# Registers_Module.net
KiCad netlist of a schematic drawn in Altium Designer
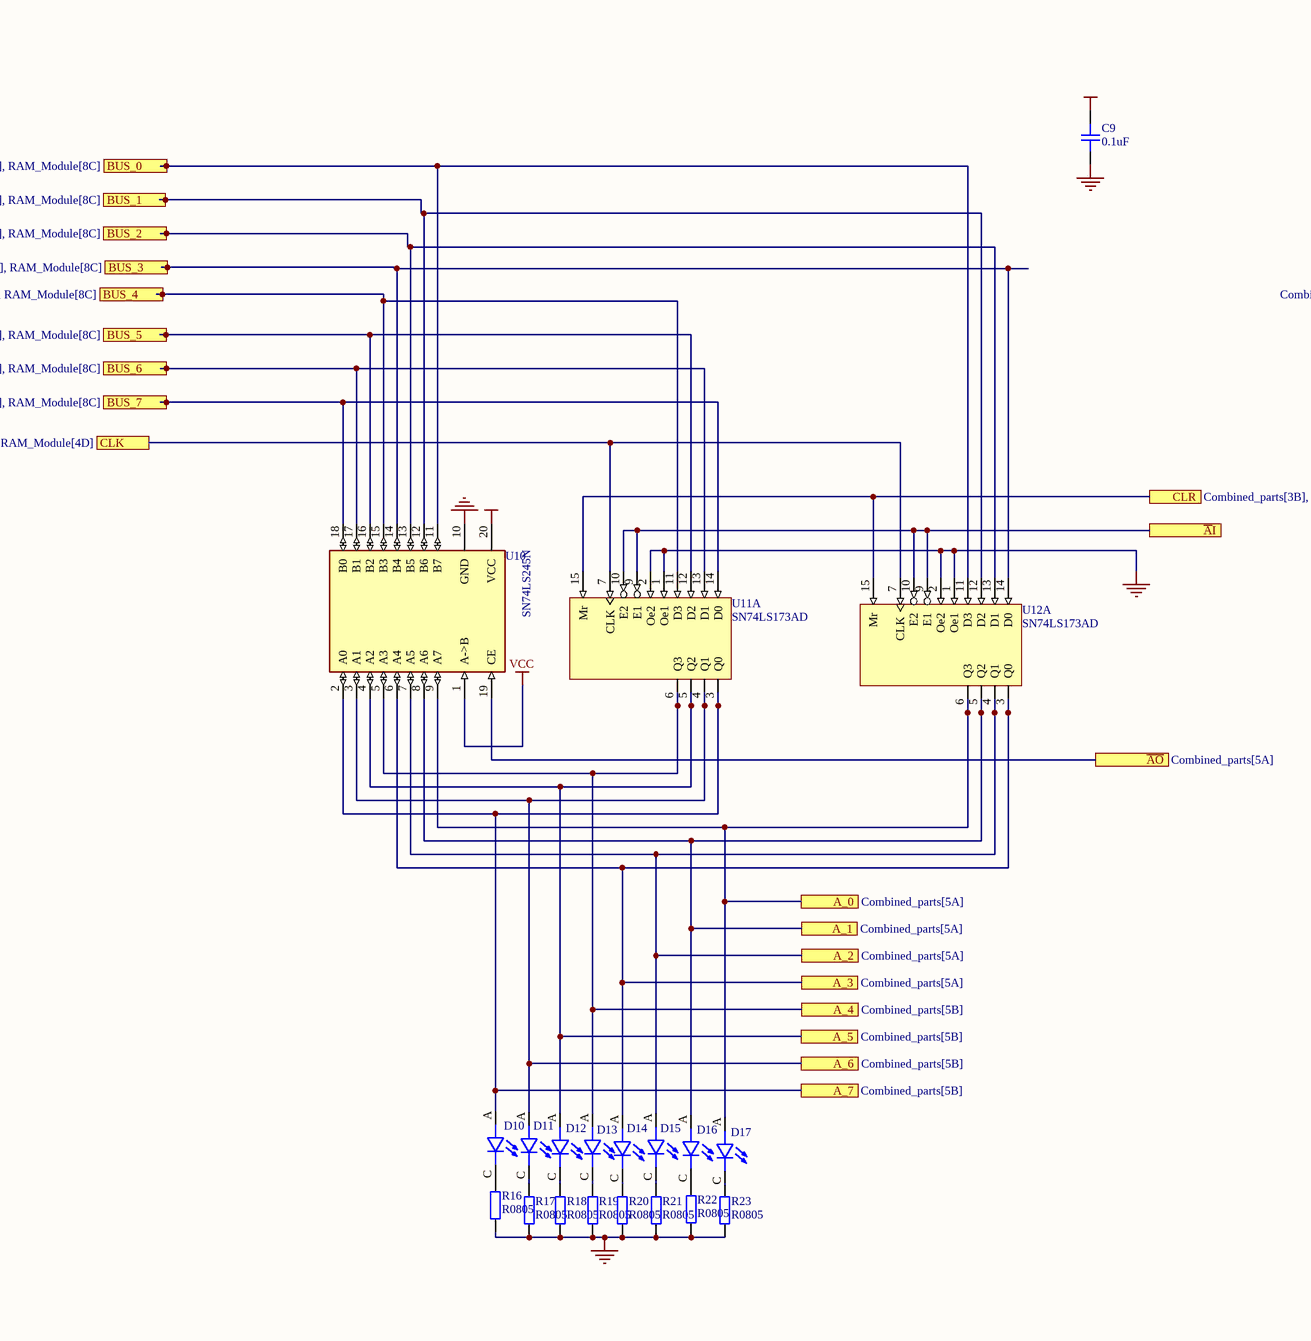
[diagram p0: Registers_Module.SchDoc, top left]
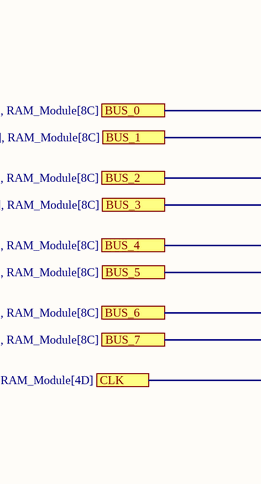
[diagram p1: Registers_Module.SchDoc, top middle]
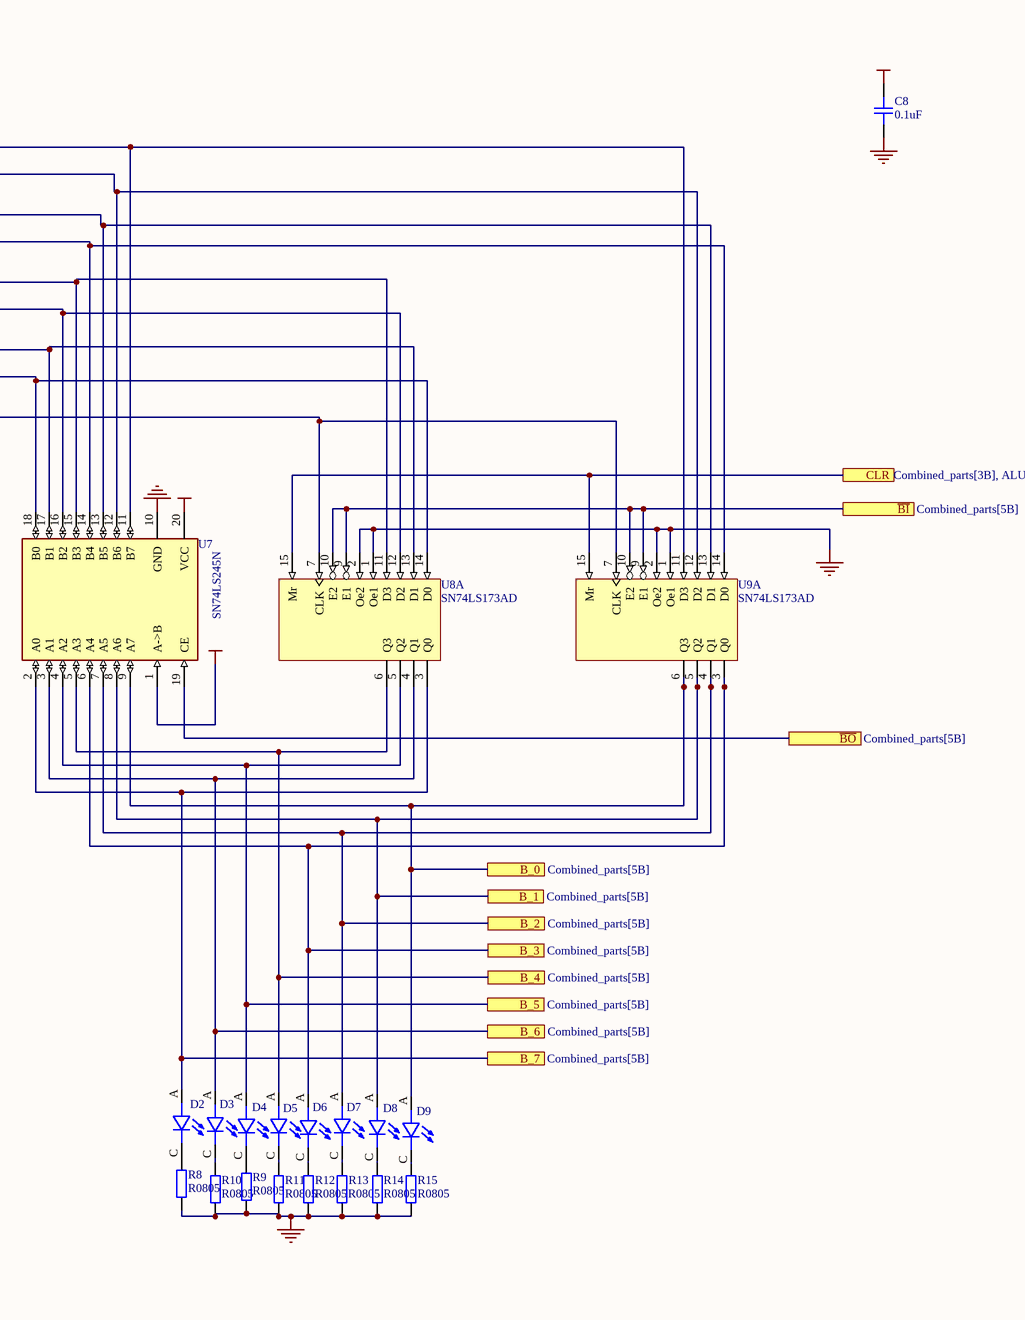
[diagram p2: Registers_Module.SchDoc, top right]
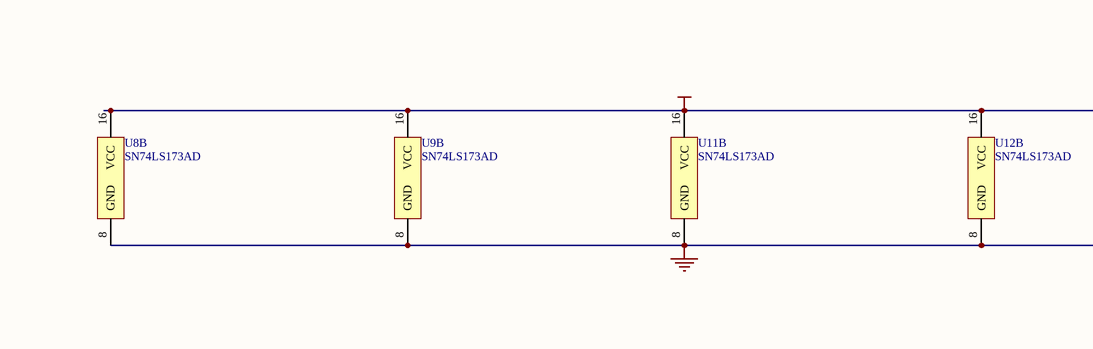
[diagram p3: Registers_Module.SchDoc, bottom left]
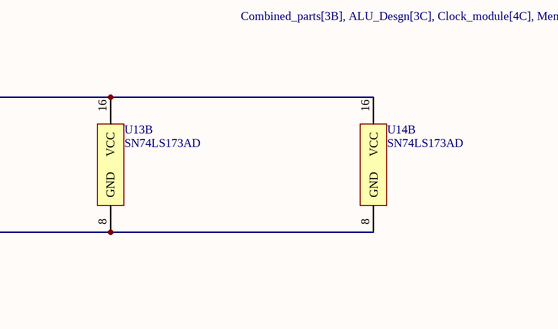
[diagram p4: Registers_Module.SchDoc, bottom middle]
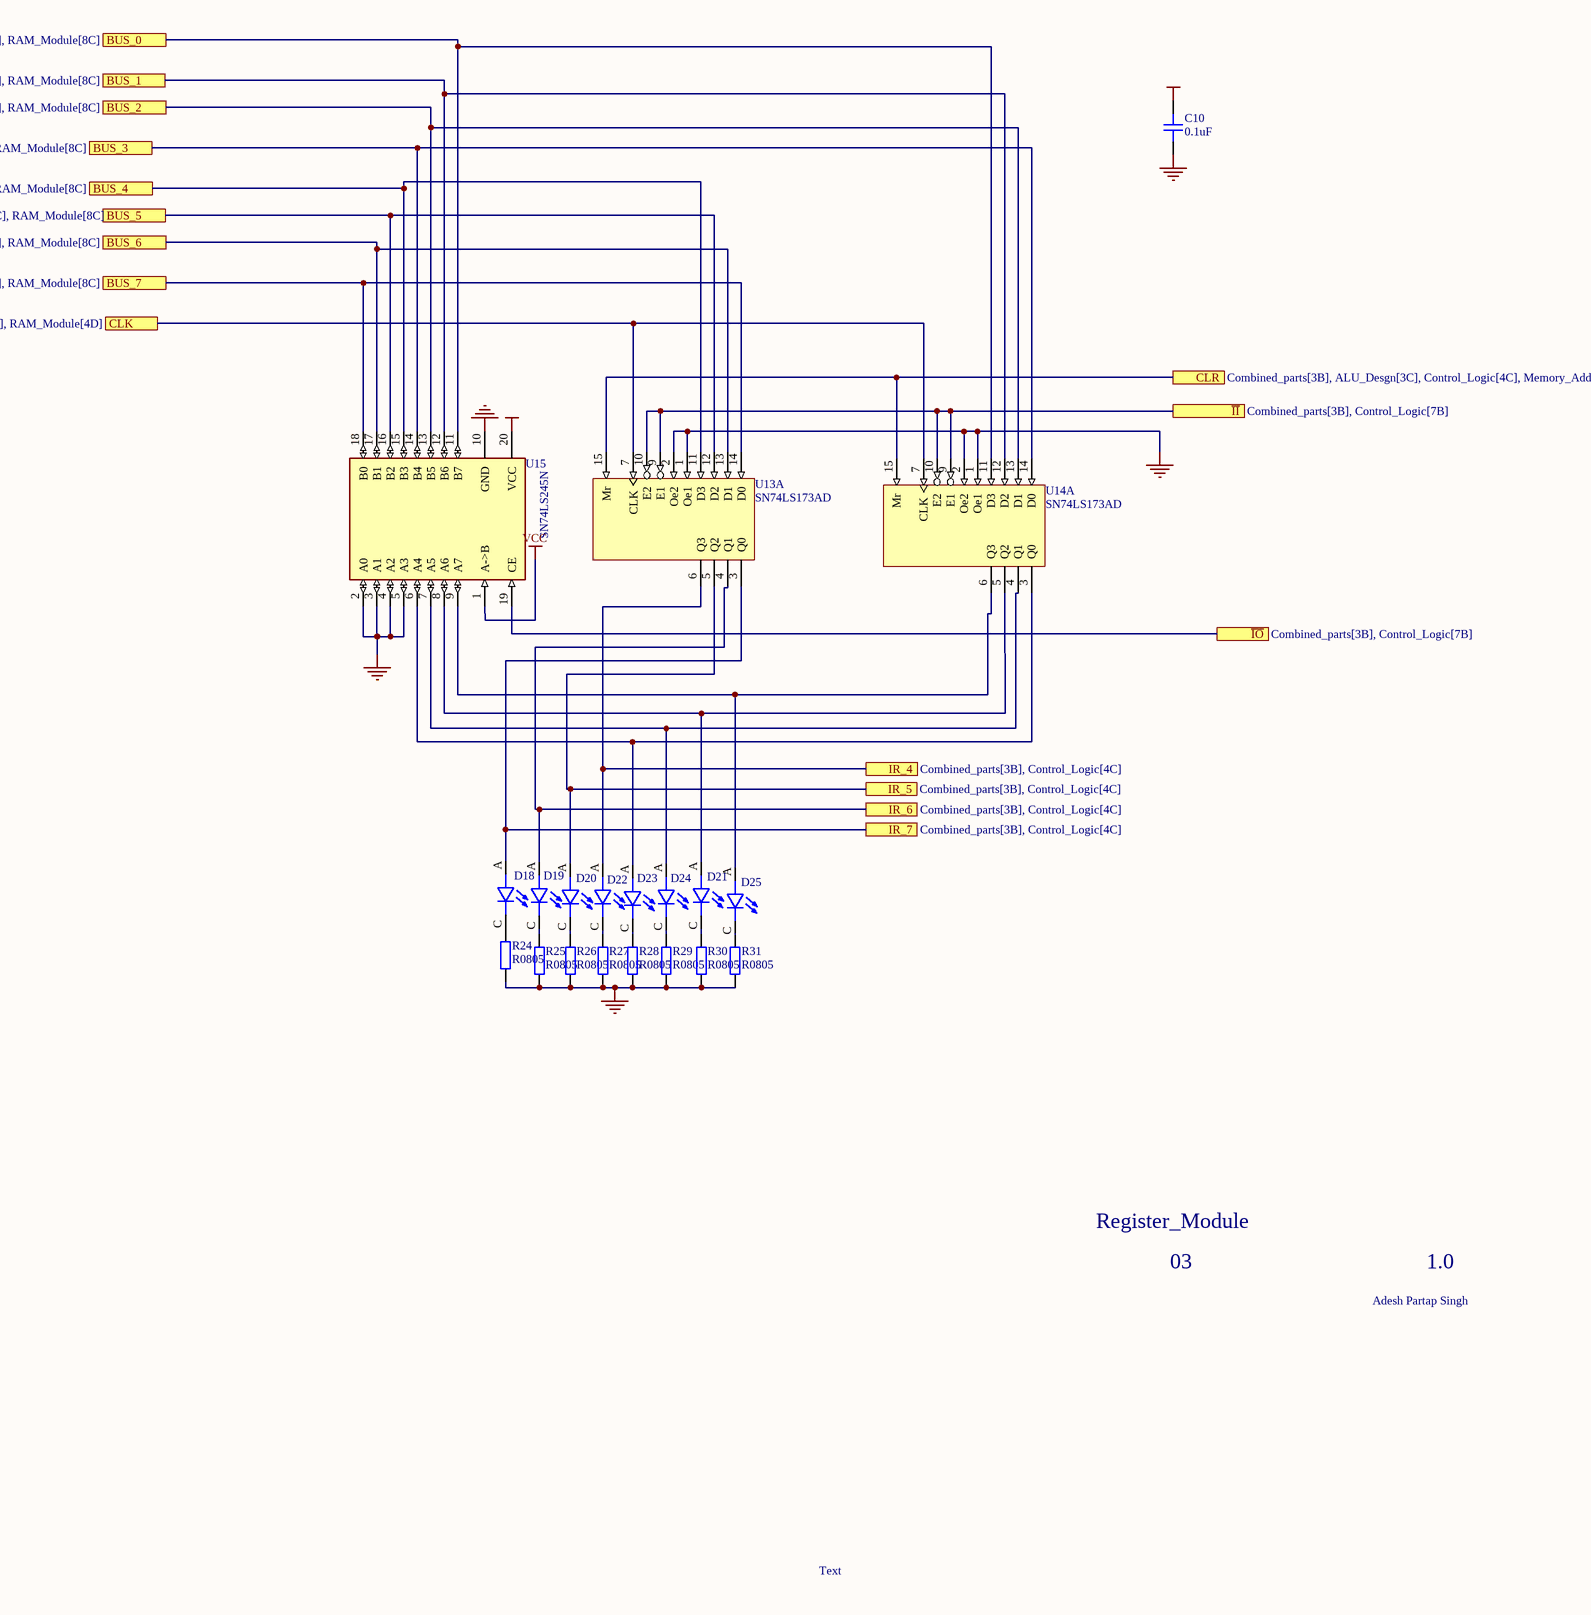
[diagram p5: Registers_Module.SchDoc, bottom right]

(export (version "E")
  (design (tool "Eeschema 10.0.6"))
  (components
    (comp (ref "C8")
      (value "0.1uF")
      (footprint "CAP_0805")
      (description "Capacitor SMD 0805")
      (libsource (lib "Schematic-Lib-PhilsLab") (part "CAP_0805"))
    )
    (comp (ref "C9")
      (value "0.1uF")
      (footprint "CAP_0805")
      (description "Capacitor SMD 0805")
      (libsource (lib "Schematic-Lib-PhilsLab") (part "CAP_0805"))
    )
    (comp (ref "C10")
      (value "0.1uF")
      (footprint "CAP_0805")
      (description "Capacitor SMD 0805")
      (libsource (lib "Schematic-Lib-PhilsLab") (part "CAP_0805"))
    )
    (comp (ref "D2")
      (value "L08R5000Q1")
      (footprint "LEDRD254W57D500H1070")
      (fields (field (name "MF") "LED Technology"))
      (libsource (lib "") (part "L08R5000Q1_1"))
    )
    (comp (ref "D3")
      (value "L08R5000Q1")
      (footprint "LEDRD254W57D500H1070")
      (fields (field (name "MF") "LED Technology"))
      (libsource (lib "") (part "L08R5000Q1_1"))
    )
    (comp (ref "D4")
      (value "L08R5000Q1")
      (footprint "LEDRD254W57D500H1070")
      (fields (field (name "MF") "LED Technology"))
      (libsource (lib "8BIT_COMP_LIB") (part "L08R5000Q1"))
    )
    (comp (ref "D5")
      (value "L08R5000Q1")
      (footprint "LEDRD254W57D500H1070")
      (fields (field (name "MF") "LED Technology"))
      (libsource (lib "") (part "L08R5000Q1_1"))
    )
    (comp (ref "D6")
      (value "L08R5000Q1")
      (footprint "LEDRD254W57D500H1070")
      (fields (field (name "MF") "LED Technology"))
      (libsource (lib "") (part "L08R5000Q1_1"))
    )
    (comp (ref "D7")
      (value "L08R5000Q1")
      (footprint "LEDRD254W57D500H1070")
      (fields (field (name "MF") "LED Technology"))
      (libsource (lib "") (part "L08R5000Q1_1"))
    )
    (comp (ref "D8")
      (value "L08R5000Q1")
      (footprint "LEDRD254W57D500H1070")
      (fields (field (name "MF") "LED Technology"))
      (libsource (lib "") (part "L08R5000Q1_1"))
    )
    (comp (ref "D9")
      (value "L08R5000Q1")
      (footprint "LEDRD254W57D500H1070")
      (fields (field (name "MF") "LED Technology"))
      (libsource (lib "") (part "L08R5000Q1_1"))
    )
    (comp (ref "D10")
      (value "L08R5000Q1")
      (footprint "LEDRD254W57D500H1070")
      (fields (field (name "MF") "LED Technology"))
      (libsource (lib "8BIT_COMP_LIB") (part "L08R5000Q1"))
    )
    (comp (ref "D11")
      (value "L08R5000Q1")
      (footprint "LEDRD254W57D500H1070")
      (fields (field (name "MF") "LED Technology"))
      (libsource (lib "8BIT_COMP_LIB") (part "L08R5000Q1"))
    )
    (comp (ref "D12")
      (value "L08R5000Q1")
      (footprint "LEDRD254W57D500H1070")
      (fields (field (name "MF") "LED Technology"))
      (libsource (lib "8BIT_COMP_LIB") (part "L08R5000Q1"))
    )
    (comp (ref "D13")
      (value "L08R5000Q1")
      (footprint "LEDRD254W57D500H1070")
      (fields (field (name "MF") "LED Technology"))
      (libsource (lib "8BIT_COMP_LIB") (part "L08R5000Q1"))
    )
    (comp (ref "D14")
      (value "L08R5000Q1")
      (footprint "LEDRD254W57D500H1070")
      (fields (field (name "MF") "LED Technology"))
      (libsource (lib "8BIT_COMP_LIB") (part "L08R5000Q1"))
    )
    (comp (ref "D15")
      (value "L08R5000Q1")
      (footprint "LEDRD254W57D500H1070")
      (fields (field (name "MF") "LED Technology"))
      (libsource (lib "8BIT_COMP_LIB") (part "L08R5000Q1"))
    )
    (comp (ref "D16")
      (value "L08R5000Q1")
      (footprint "LEDRD254W57D500H1070")
      (fields (field (name "MF") "LED Technology"))
      (libsource (lib "8BIT_COMP_LIB") (part "L08R5000Q1"))
    )
    (comp (ref "D17")
      (value "L08R5000Q1")
      (footprint "LEDRD254W57D500H1070")
      (fields (field (name "MF") "LED Technology"))
      (libsource (lib "8BIT_COMP_LIB") (part "L08R5000Q1"))
    )
    (comp (ref "D18")
      (value "L08R5000Q1")
      (footprint "LEDRD254W57D500H1070")
      (fields (field (name "MF") "LED Technology"))
      (libsource (lib "8BIT_COMP_LIB") (part "L08R5000Q1"))
    )
    (comp (ref "D19")
      (value "L08R5000Q1")
      (footprint "LEDRD254W57D500H1070")
      (fields (field (name "MF") "LED Technology"))
      (libsource (lib "8BIT_COMP_LIB") (part "L08R5000Q1"))
    )
    (comp (ref "D20")
      (value "L08R5000Q1")
      (footprint "LEDRD254W57D500H1070")
      (fields (field (name "MF") "LED Technology"))
      (libsource (lib "8BIT_COMP_LIB") (part "L08R5000Q1"))
    )
    (comp (ref "D21")
      (value "L08R5000Q1")
      (footprint "LEDRD254W57D500H1070")
      (fields (field (name "MF") "LED Technology"))
      (libsource (lib "8BIT_COMP_LIB") (part "L08R5000Q1"))
    )
    (comp (ref "D22")
      (value "L08R5000Q1")
      (footprint "LEDRD254W57D500H1070")
      (fields (field (name "MF") "LED Technology"))
      (libsource (lib "8BIT_COMP_LIB") (part "L08R5000Q1"))
    )
    (comp (ref "D23")
      (value "L08R5000Q1")
      (footprint "LEDRD254W57D500H1070")
      (fields (field (name "MF") "LED Technology"))
      (libsource (lib "8BIT_COMP_LIB") (part "L08R5000Q1"))
    )
    (comp (ref "D24")
      (value "L08R5000Q1")
      (footprint "LEDRD254W57D500H1070")
      (fields (field (name "MF") "LED Technology"))
      (libsource (lib "8BIT_COMP_LIB") (part "L08R5000Q1"))
    )
    (comp (ref "D25")
      (value "L08R5000Q1")
      (footprint "LEDRD254W57D500H1070")
      (fields (field (name "MF") "LED Technology"))
      (libsource (lib "8BIT_COMP_LIB") (part "L08R5000Q1"))
    )
    (comp (ref "R8")
      (value "R0805")
      (footprint "RES_0805")
      (description "Resistor SMD 0805")
      (libsource (lib "Schematic-Lib-PhilsLab") (part "RES_0805"))
    )
    (comp (ref "R9")
      (value "R0805")
      (footprint "RES_0805")
      (description "Resistor SMD 0805")
      (libsource (lib "Schematic-Lib-PhilsLab") (part "RES_0805"))
    )
    (comp (ref "R10")
      (value "R0805")
      (footprint "RES_0805")
      (description "Resistor SMD 0805")
      (libsource (lib "Schematic-Lib-PhilsLab") (part "RES_0805"))
    )
    (comp (ref "R11")
      (value "R0805")
      (footprint "RES_0805")
      (description "Resistor SMD 0805")
      (libsource (lib "Schematic-Lib-PhilsLab") (part "RES_0805"))
    )
    (comp (ref "R12")
      (value "R0805")
      (footprint "RES_0805")
      (description "Resistor SMD 0805")
      (libsource (lib "Schematic-Lib-PhilsLab") (part "RES_0805"))
    )
    (comp (ref "R13")
      (value "R0805")
      (footprint "RES_0805")
      (description "Resistor SMD 0805")
      (libsource (lib "Schematic-Lib-PhilsLab") (part "RES_0805"))
    )
    (comp (ref "R14")
      (value "R0805")
      (footprint "RES_0805")
      (description "Resistor SMD 0805")
      (libsource (lib "Schematic-Lib-PhilsLab") (part "RES_0805"))
    )
    (comp (ref "R15")
      (value "R0805")
      (footprint "RES_0805")
      (description "Resistor SMD 0805")
      (libsource (lib "Schematic-Lib-PhilsLab") (part "RES_0805"))
    )
    (comp (ref "R16")
      (value "R0805")
      (footprint "RES_0805")
      (description "Resistor SMD 0805")
      (libsource (lib "Schematic-Lib-PhilsLab") (part "RES_0805"))
    )
    (comp (ref "R17")
      (value "R0805")
      (footprint "RES_0805")
      (description "Resistor SMD 0805")
      (libsource (lib "Schematic-Lib-PhilsLab") (part "RES_0805"))
    )
    (comp (ref "R18")
      (value "R0805")
      (footprint "RES_0805")
      (description "Resistor SMD 0805")
      (libsource (lib "Schematic-Lib-PhilsLab") (part "RES_0805"))
    )
    (comp (ref "R19")
      (value "R0805")
      (footprint "RES_0805")
      (description "Resistor SMD 0805")
      (libsource (lib "Schematic-Lib-PhilsLab") (part "RES_0805"))
    )
    (comp (ref "R20")
      (value "R0805")
      (footprint "RES_0805")
      (description "Resistor SMD 0805")
      (libsource (lib "Schematic-Lib-PhilsLab") (part "RES_0805"))
    )
    (comp (ref "R21")
      (value "R0805")
      (footprint "RES_0805")
      (description "Resistor SMD 0805")
      (libsource (lib "Schematic-Lib-PhilsLab") (part "RES_0805"))
    )
    (comp (ref "R22")
      (value "R0805")
      (footprint "RES_0805")
      (description "Resistor SMD 0805")
      (libsource (lib "Schematic-Lib-PhilsLab") (part "RES_0805"))
    )
    (comp (ref "R23")
      (value "R0805")
      (footprint "RES_0805")
      (description "Resistor SMD 0805")
      (libsource (lib "Schematic-Lib-PhilsLab") (part "RES_0805"))
    )
    (comp (ref "R24")
      (value "R0805")
      (footprint "RES_0805")
      (description "Resistor SMD 0805")
      (libsource (lib "Schematic-Lib-PhilsLab") (part "RES_0805"))
    )
    (comp (ref "R25")
      (value "R0805")
      (footprint "RES_0805")
      (description "Resistor SMD 0805")
      (libsource (lib "Schematic-Lib-PhilsLab") (part "RES_0805"))
    )
    (comp (ref "R26")
      (value "R0805")
      (footprint "RES_0805")
      (description "Resistor SMD 0805")
      (libsource (lib "Schematic-Lib-PhilsLab") (part "RES_0805"))
    )
    (comp (ref "R27")
      (value "R0805")
      (footprint "RES_0805")
      (description "Resistor SMD 0805")
      (libsource (lib "Schematic-Lib-PhilsLab") (part "RES_0805"))
    )
    (comp (ref "R28")
      (value "R0805")
      (footprint "RES_0805")
      (description "Resistor SMD 0805")
      (libsource (lib "Schematic-Lib-PhilsLab") (part "RES_0805"))
    )
    (comp (ref "R29")
      (value "R0805")
      (footprint "RES_0805")
      (description "Resistor SMD 0805")
      (libsource (lib "Schematic-Lib-PhilsLab") (part "RES_0805"))
    )
    (comp (ref "R30")
      (value "R0805")
      (footprint "RES_0805")
      (description "Resistor SMD 0805")
      (libsource (lib "Schematic-Lib-PhilsLab") (part "RES_0805"))
    )
    (comp (ref "R31")
      (value "R0805")
      (footprint "RES_0805")
      (description "Resistor SMD 0805")
      (libsource (lib "Schematic-Lib-PhilsLab") (part "RES_0805"))
    )
    (comp (ref "U7")
      (value "SN74LS245N")
      (footprint "FP-N0020A-MFG")
      (description "IC TXRX NON-INVERT 5.25V 20DIP")
      (libsource (lib "8BIT_COMP_LIB") (part "CMP-1620-00419-3"))
    )
    (comp (ref "U8")
      (value "SN74LS173AD")
      (footprint "D0016A_N")
      (description "4-Bit D-type Registers with 3-State Outputs, D0016A, TUBE")
      (fields
        (field (name "GENERIC PART NUMBER") "SN74LS173A")
        (field (name "MANUFACTURER") "Texas Instruments")
      )
      (libsource (lib "") (part "CMP-1616-00008-3_1"))
    )
    (comp (ref "U9")
      (value "SN74LS173AD")
      (footprint "D0016A_N")
      (description "4-Bit D-type Registers with 3-State Outputs, D0016A, TUBE")
      (fields
        (field (name "GENERIC PART NUMBER") "SN74LS173A")
        (field (name "MANUFACTURER") "Texas Instruments")
      )
      (libsource (lib "") (part "CMP-1616-00008-3_1"))
    )
    (comp (ref "U10")
      (value "SN74LS245N")
      (footprint "FP-N0020A-MFG")
      (description "IC TXRX NON-INVERT 5.25V 20DIP")
      (libsource (lib "8BIT_COMP_LIB") (part "CMP-1620-00419-3"))
    )
    (comp (ref "U11")
      (value "SN74LS173AD")
      (footprint "D0016A_N")
      (description "4-Bit D-type Registers with 3-State Outputs, D0016A, TUBE")
      (fields
        (field (name "GENERIC PART NUMBER") "SN74LS173A")
        (field (name "MANUFACTURER") "Texas Instruments")
      )
      (libsource (lib "") (part "CMP-1616-00008-3_1"))
    )
    (comp (ref "U12")
      (value "SN74LS173AD")
      (footprint "D0016A_N")
      (description "4-Bit D-type Registers with 3-State Outputs, D0016A, TUBE")
      (fields
        (field (name "GENERIC PART NUMBER") "SN74LS173A")
        (field (name "MANUFACTURER") "Texas Instruments")
      )
      (libsource (lib "") (part "CMP-1616-00008-3_1"))
    )
    (comp (ref "U13")
      (value "SN74LS173AD")
      (footprint "D0016A_N")
      (description "4-Bit D-type Registers with 3-State Outputs, D0016A, TUBE")
      (fields
        (field (name "GENERIC PART NUMBER") "SN74LS173A")
        (field (name "MANUFACTURER") "Texas Instruments")
      )
      (libsource (lib "") (part "CMP-1616-00008-3_1"))
    )
    (comp (ref "U14")
      (value "SN74LS173AD")
      (footprint "D0016A_N")
      (description "4-Bit D-type Registers with 3-State Outputs, D0016A, TUBE")
      (fields
        (field (name "GENERIC PART NUMBER") "SN74LS173A")
        (field (name "MANUFACTURER") "Texas Instruments")
      )
      (libsource (lib "8BIT_COMP_LIB") (part "CMP-1616-00008-3"))
    )
    (comp (ref "U15")
      (value "SN74LS245N")
      (footprint "FP-N0020A-MFG")
      (description "IC TXRX NON-INVERT 5.25V 20DIP")
      (libsource (lib "8BIT_COMP_LIB") (part "CMP-1620-00419-3"))
    )
  )
  (nets
    (net (code "1") (name "/A_0") (class "Default")
      (node (ref "D17") (pin "A") (pinfunction "A_A") (pintype "passive"))
      (node (ref "U10") (pin "9") (pinfunction "A7_9") (pintype "bidirectional"))
      (node (ref "U12") (pin "6") (pinfunction "Q3_6") (pintype "tri_state"))
    )
    (net (code "2") (name "/A_1") (class "Default")
      (node (ref "D16") (pin "A") (pinfunction "A_A") (pintype "passive"))
      (node (ref "U10") (pin "8") (pinfunction "A6_8") (pintype "bidirectional"))
      (node (ref "U12") (pin "5") (pinfunction "Q2_5") (pintype "tri_state"))
    )
    (net (code "3") (name "/A_2") (class "Default")
      (node (ref "D15") (pin "A") (pinfunction "A_A") (pintype "passive"))
      (node (ref "U10") (pin "7") (pinfunction "A5_7") (pintype "bidirectional"))
      (node (ref "U12") (pin "4") (pinfunction "Q1_4") (pintype "tri_state"))
    )
    (net (code "4") (name "/A_3") (class "Default")
      (node (ref "D14") (pin "A") (pinfunction "A_A") (pintype "passive"))
      (node (ref "U10") (pin "6") (pinfunction "A4_6") (pintype "bidirectional"))
      (node (ref "U12") (pin "3") (pinfunction "Q0_3") (pintype "tri_state"))
    )
    (net (code "5") (name "/A_4") (class "Default")
      (node (ref "D13") (pin "A") (pinfunction "A_A") (pintype "passive"))
      (node (ref "U10") (pin "5") (pinfunction "A3_5") (pintype "bidirectional"))
      (node (ref "U11") (pin "6") (pinfunction "Q3_6") (pintype "tri_state"))
    )
    (net (code "6") (name "/A_5") (class "Default")
      (node (ref "D12") (pin "A") (pinfunction "A_A") (pintype "passive"))
      (node (ref "U10") (pin "4") (pinfunction "A2_4") (pintype "bidirectional"))
      (node (ref "U11") (pin "5") (pinfunction "Q2_5") (pintype "tri_state"))
    )
    (net (code "7") (name "/A_6") (class "Default")
      (node (ref "D11") (pin "A") (pinfunction "A_A") (pintype "passive"))
      (node (ref "U10") (pin "3") (pinfunction "A1_3") (pintype "bidirectional"))
      (node (ref "U11") (pin "4") (pinfunction "Q1_4") (pintype "tri_state"))
    )
    (net (code "8") (name "/A_7") (class "Default")
      (node (ref "D10") (pin "A") (pinfunction "A_A") (pintype "passive"))
      (node (ref "U10") (pin "2") (pinfunction "A0_2") (pintype "bidirectional"))
      (node (ref "U11") (pin "3") (pinfunction "Q0_3") (pintype "tri_state"))
    )
    (net (code "9") (name "/BUS_0") (class "Default")
      (node (ref "U10") (pin "11") (pinfunction "B7_11") (pintype "bidirectional"))
      (node (ref "U12") (pin "11") (pinfunction "D3_11") (pintype "input"))
      (node (ref "U14") (pin "11") (pinfunction "D3_11") (pintype "input"))
      (node (ref "U15") (pin "11") (pinfunction "B7_11") (pintype "bidirectional"))
      (node (ref "U7") (pin "11") (pinfunction "B7_11") (pintype "bidirectional"))
      (node (ref "U9") (pin "11") (pinfunction "D3_11") (pintype "input"))
    )
    (net (code "10") (name "/BUS_1") (class "Default")
      (node (ref "U10") (pin "12") (pinfunction "B6_12") (pintype "bidirectional"))
      (node (ref "U12") (pin "12") (pinfunction "D2_12") (pintype "input"))
      (node (ref "U14") (pin "12") (pinfunction "D2_12") (pintype "input"))
      (node (ref "U15") (pin "12") (pinfunction "B6_12") (pintype "bidirectional"))
      (node (ref "U7") (pin "12") (pinfunction "B6_12") (pintype "bidirectional"))
      (node (ref "U9") (pin "12") (pinfunction "D2_12") (pintype "input"))
    )
    (net (code "11") (name "/BUS_2") (class "Default")
      (node (ref "U10") (pin "13") (pinfunction "B5_13") (pintype "bidirectional"))
      (node (ref "U12") (pin "13") (pinfunction "D1_13") (pintype "input"))
      (node (ref "U14") (pin "13") (pinfunction "D1_13") (pintype "input"))
      (node (ref "U15") (pin "13") (pinfunction "B5_13") (pintype "bidirectional"))
      (node (ref "U7") (pin "13") (pinfunction "B5_13") (pintype "bidirectional"))
      (node (ref "U9") (pin "13") (pinfunction "D1_13") (pintype "input"))
    )
    (net (code "12") (name "/BUS_3") (class "Default")
      (node (ref "U10") (pin "14") (pinfunction "B4_14") (pintype "bidirectional"))
      (node (ref "U12") (pin "14") (pinfunction "D0_14") (pintype "input"))
      (node (ref "U14") (pin "14") (pinfunction "D0_14") (pintype "input"))
      (node (ref "U15") (pin "14") (pinfunction "B4_14") (pintype "bidirectional"))
      (node (ref "U7") (pin "14") (pinfunction "B4_14") (pintype "bidirectional"))
      (node (ref "U9") (pin "14") (pinfunction "D0_14") (pintype "input"))
    )
    (net (code "13") (name "/BUS_4") (class "Default")
      (node (ref "U10") (pin "15") (pinfunction "B3_15") (pintype "bidirectional"))
      (node (ref "U11") (pin "11") (pinfunction "D3_11") (pintype "input"))
      (node (ref "U13") (pin "11") (pinfunction "D3_11") (pintype "input"))
      (node (ref "U15") (pin "15") (pinfunction "B3_15") (pintype "bidirectional"))
      (node (ref "U7") (pin "15") (pinfunction "B3_15") (pintype "bidirectional"))
      (node (ref "U8") (pin "11") (pinfunction "D3_11") (pintype "input"))
    )
    (net (code "14") (name "/BUS_5") (class "Default")
      (node (ref "U10") (pin "16") (pinfunction "B2_16") (pintype "bidirectional"))
      (node (ref "U11") (pin "12") (pinfunction "D2_12") (pintype "input"))
      (node (ref "U13") (pin "12") (pinfunction "D2_12") (pintype "input"))
      (node (ref "U15") (pin "16") (pinfunction "B2_16") (pintype "bidirectional"))
      (node (ref "U7") (pin "16") (pinfunction "B2_16") (pintype "bidirectional"))
      (node (ref "U8") (pin "12") (pinfunction "D2_12") (pintype "input"))
    )
    (net (code "15") (name "/BUS_6") (class "Default")
      (node (ref "U10") (pin "17") (pinfunction "B1_17") (pintype "bidirectional"))
      (node (ref "U11") (pin "13") (pinfunction "D1_13") (pintype "input"))
      (node (ref "U13") (pin "13") (pinfunction "D1_13") (pintype "input"))
      (node (ref "U15") (pin "17") (pinfunction "B1_17") (pintype "bidirectional"))
      (node (ref "U7") (pin "17") (pinfunction "B1_17") (pintype "bidirectional"))
      (node (ref "U8") (pin "13") (pinfunction "D1_13") (pintype "input"))
    )
    (net (code "16") (name "/BUS_7") (class "Default")
      (node (ref "U10") (pin "18") (pinfunction "B0_18") (pintype "bidirectional"))
      (node (ref "U11") (pin "14") (pinfunction "D0_14") (pintype "input"))
      (node (ref "U13") (pin "14") (pinfunction "D0_14") (pintype "input"))
      (node (ref "U15") (pin "18") (pinfunction "B0_18") (pintype "bidirectional"))
      (node (ref "U7") (pin "18") (pinfunction "B0_18") (pintype "bidirectional"))
      (node (ref "U8") (pin "14") (pinfunction "D0_14") (pintype "input"))
    )
    (net (code "17") (name "/B_0") (class "Default")
      (node (ref "D9") (pin "A") (pinfunction "A_A") (pintype "passive"))
      (node (ref "U7") (pin "9") (pinfunction "A7_9") (pintype "bidirectional"))
      (node (ref "U9") (pin "6") (pinfunction "Q3_6") (pintype "tri_state"))
    )
    (net (code "18") (name "/B_1") (class "Default")
      (node (ref "D8") (pin "A") (pinfunction "A_A") (pintype "passive"))
      (node (ref "U7") (pin "8") (pinfunction "A6_8") (pintype "bidirectional"))
      (node (ref "U9") (pin "5") (pinfunction "Q2_5") (pintype "tri_state"))
    )
    (net (code "19") (name "/B_2") (class "Default")
      (node (ref "D7") (pin "A") (pinfunction "A_A") (pintype "passive"))
      (node (ref "U7") (pin "7") (pinfunction "A5_7") (pintype "bidirectional"))
      (node (ref "U9") (pin "4") (pinfunction "Q1_4") (pintype "tri_state"))
    )
    (net (code "20") (name "/B_3") (class "Default")
      (node (ref "D6") (pin "A") (pinfunction "A_A") (pintype "passive"))
      (node (ref "U7") (pin "6") (pinfunction "A4_6") (pintype "bidirectional"))
      (node (ref "U9") (pin "3") (pinfunction "Q0_3") (pintype "tri_state"))
    )
    (net (code "21") (name "/B_4") (class "Default")
      (node (ref "D5") (pin "A") (pinfunction "A_A") (pintype "passive"))
      (node (ref "U7") (pin "5") (pinfunction "A3_5") (pintype "bidirectional"))
      (node (ref "U8") (pin "6") (pinfunction "Q3_6") (pintype "tri_state"))
    )
    (net (code "22") (name "/B_5") (class "Default")
      (node (ref "D4") (pin "A") (pinfunction "A_A") (pintype "passive"))
      (node (ref "U7") (pin "4") (pinfunction "A2_4") (pintype "bidirectional"))
      (node (ref "U8") (pin "5") (pinfunction "Q2_5") (pintype "tri_state"))
    )
    (net (code "23") (name "/B_6") (class "Default")
      (node (ref "D3") (pin "A") (pinfunction "A_A") (pintype "passive"))
      (node (ref "U7") (pin "3") (pinfunction "A1_3") (pintype "bidirectional"))
      (node (ref "U8") (pin "4") (pinfunction "Q1_4") (pintype "tri_state"))
    )
    (net (code "24") (name "/B_7") (class "Default")
      (node (ref "D2") (pin "A") (pinfunction "A_A") (pintype "passive"))
      (node (ref "U7") (pin "2") (pinfunction "A0_2") (pintype "bidirectional"))
      (node (ref "U8") (pin "3") (pinfunction "Q0_3") (pintype "tri_state"))
    )
    (net (code "25") (name "/CLK") (class "Default")
      (node (ref "U11") (pin "7") (pinfunction "CLK_7") (pintype "input"))
      (node (ref "U12") (pin "7") (pinfunction "CLK_7") (pintype "input"))
      (node (ref "U13") (pin "7") (pinfunction "CLK_7") (pintype "input"))
      (node (ref "U14") (pin "7") (pinfunction "CLK_7") (pintype "input"))
      (node (ref "U8") (pin "7") (pinfunction "CLK_7") (pintype "input"))
      (node (ref "U9") (pin "7") (pinfunction "CLK_7") (pintype "input"))
    )
    (net (code "26") (name "/CLR") (class "Default")
      (node (ref "U11") (pin "15") (pinfunction "Mr_15") (pintype "input"))
      (node (ref "U12") (pin "15") (pinfunction "Mr_15") (pintype "input"))
      (node (ref "U13") (pin "15") (pinfunction "Mr_15") (pintype "input"))
      (node (ref "U14") (pin "15") (pinfunction "Mr_15") (pintype "input"))
      (node (ref "U8") (pin "15") (pinfunction "Mr_15") (pintype "input"))
      (node (ref "U9") (pin "15") (pinfunction "Mr_15") (pintype "input"))
    )
    (net (code "27") (name "/IR_4") (class "Default")
      (node (ref "D22") (pin "A") (pinfunction "A_A") (pintype "passive"))
      (node (ref "U13") (pin "6") (pinfunction "Q3_6") (pintype "tri_state"))
    )
    (net (code "28") (name "/IR_5") (class "Default")
      (node (ref "D20") (pin "A") (pinfunction "A_A") (pintype "passive"))
      (node (ref "U13") (pin "5") (pinfunction "Q2_5") (pintype "tri_state"))
    )
    (net (code "29") (name "/IR_6") (class "Default")
      (node (ref "D19") (pin "A") (pinfunction "A_A") (pintype "passive"))
      (node (ref "U13") (pin "4") (pinfunction "Q1_4") (pintype "tri_state"))
    )
    (net (code "30") (name "/IR_7") (class "Default")
      (node (ref "D18") (pin "A") (pinfunction "A_A") (pintype "passive"))
      (node (ref "U13") (pin "3") (pinfunction "Q0_3") (pintype "tri_state"))
    )
    (net (code "31") (name "/~{AO}") (class "Default")
      (node (ref "U10") (pin "19") (pinfunction "CE_19") (pintype "input"))
    )
    (net (code "32") (name "/~{A}I") (class "Default")
      (node (ref "U11") (pin "10") (pinfunction "E2_10") (pintype "input"))
      (node (ref "U11") (pin "9") (pinfunction "E1_9") (pintype "input"))
      (node (ref "U12") (pin "10") (pinfunction "E2_10") (pintype "input"))
      (node (ref "U12") (pin "9") (pinfunction "E1_9") (pintype "input"))
    )
    (net (code "33") (name "/~{BI}") (class "Default")
      (node (ref "U8") (pin "10") (pinfunction "E2_10") (pintype "input"))
      (node (ref "U8") (pin "9") (pinfunction "E1_9") (pintype "input"))
      (node (ref "U9") (pin "10") (pinfunction "E2_10") (pintype "input"))
      (node (ref "U9") (pin "9") (pinfunction "E1_9") (pintype "input"))
    )
    (net (code "34") (name "/~{BO}") (class "Default")
      (node (ref "U7") (pin "19") (pinfunction "CE_19") (pintype "input"))
    )
    (net (code "35") (name "/~{II}") (class "Default")
      (node (ref "U13") (pin "10") (pinfunction "E2_10") (pintype "input"))
      (node (ref "U13") (pin "9") (pinfunction "E1_9") (pintype "input"))
      (node (ref "U14") (pin "10") (pinfunction "E2_10") (pintype "input"))
      (node (ref "U14") (pin "9") (pinfunction "E1_9") (pintype "input"))
    )
    (net (code "36") (name "/~{IO}") (class "Default")
      (node (ref "U15") (pin "19") (pinfunction "CE_19") (pintype "input"))
    )
    (net (code "37") (name "GND") (class "Default")
      (node (ref "C10") (pin "1") (pinfunction "1_1") (pintype "passive"))
      (node (ref "C8") (pin "1") (pinfunction "1_1") (pintype "passive"))
      (node (ref "C9") (pin "1") (pinfunction "1_1") (pintype "passive"))
      (node (ref "R10") (pin "1") (pinfunction "1_1") (pintype "passive"))
      (node (ref "R11") (pin "1") (pinfunction "1_1") (pintype "passive"))
      (node (ref "R12") (pin "1") (pinfunction "1_1") (pintype "passive"))
      (node (ref "R13") (pin "1") (pinfunction "1_1") (pintype "passive"))
      (node (ref "R14") (pin "1") (pinfunction "1_1") (pintype "passive"))
      (node (ref "R15") (pin "1") (pinfunction "1_1") (pintype "passive"))
      (node (ref "R16") (pin "1") (pinfunction "1_1") (pintype "passive"))
      (node (ref "R17") (pin "1") (pinfunction "1_1") (pintype "passive"))
      (node (ref "R18") (pin "1") (pinfunction "1_1") (pintype "passive"))
      (node (ref "R19") (pin "1") (pinfunction "1_1") (pintype "passive"))
      (node (ref "R20") (pin "1") (pinfunction "1_1") (pintype "passive"))
      (node (ref "R21") (pin "1") (pinfunction "1_1") (pintype "passive"))
      (node (ref "R22") (pin "1") (pinfunction "1_1") (pintype "passive"))
      (node (ref "R23") (pin "1") (pinfunction "1_1") (pintype "passive"))
      (node (ref "R24") (pin "1") (pinfunction "1_1") (pintype "passive"))
      (node (ref "R25") (pin "1") (pinfunction "1_1") (pintype "passive"))
      (node (ref "R26") (pin "1") (pinfunction "1_1") (pintype "passive"))
      (node (ref "R27") (pin "1") (pinfunction "1_1") (pintype "passive"))
      (node (ref "R28") (pin "1") (pinfunction "1_1") (pintype "passive"))
      (node (ref "R29") (pin "1") (pinfunction "1_1") (pintype "passive"))
      (node (ref "R30") (pin "1") (pinfunction "1_1") (pintype "passive"))
      (node (ref "R31") (pin "1") (pinfunction "1_1") (pintype "passive"))
      (node (ref "R8") (pin "1") (pinfunction "1_1") (pintype "passive"))
      (node (ref "R9") (pin "1") (pinfunction "1_1") (pintype "passive"))
      (node (ref "U10") (pin "10") (pinfunction "GND_10") (pintype "power_in"))
      (node (ref "U11") (pin "1") (pinfunction "Oe1_1") (pintype "input"))
      (node (ref "U11") (pin "2") (pinfunction "Oe2_2") (pintype "input"))
      (node (ref "U11") (pin "8") (pinfunction "GND_8") (pintype "power_in"))
      (node (ref "U12") (pin "1") (pinfunction "Oe1_1") (pintype "input"))
      (node (ref "U12") (pin "2") (pinfunction "Oe2_2") (pintype "input"))
      (node (ref "U12") (pin "8") (pinfunction "GND_8") (pintype "power_in"))
      (node (ref "U13") (pin "1") (pinfunction "Oe1_1") (pintype "input"))
      (node (ref "U13") (pin "2") (pinfunction "Oe2_2") (pintype "input"))
      (node (ref "U13") (pin "8") (pinfunction "GND_8") (pintype "power_in"))
      (node (ref "U14") (pin "1") (pinfunction "Oe1_1") (pintype "input"))
      (node (ref "U14") (pin "2") (pinfunction "Oe2_2") (pintype "input"))
      (node (ref "U14") (pin "8") (pinfunction "GND_8") (pintype "power_in"))
      (node (ref "U15") (pin "10") (pinfunction "GND_10") (pintype "power_in"))
      (node (ref "U15") (pin "2") (pinfunction "A0_2") (pintype "bidirectional"))
      (node (ref "U15") (pin "3") (pinfunction "A1_3") (pintype "bidirectional"))
      (node (ref "U15") (pin "4") (pinfunction "A2_4") (pintype "bidirectional"))
      (node (ref "U15") (pin "5") (pinfunction "A3_5") (pintype "bidirectional"))
      (node (ref "U7") (pin "10") (pinfunction "GND_10") (pintype "power_in"))
      (node (ref "U8") (pin "1") (pinfunction "Oe1_1") (pintype "input"))
      (node (ref "U8") (pin "2") (pinfunction "Oe2_2") (pintype "input"))
      (node (ref "U8") (pin "8") (pinfunction "GND_8") (pintype "power_in"))
      (node (ref "U9") (pin "1") (pinfunction "Oe1_1") (pintype "input"))
      (node (ref "U9") (pin "2") (pinfunction "Oe2_2") (pintype "input"))
      (node (ref "U9") (pin "8") (pinfunction "GND_8") (pintype "power_in"))
    )
    (net (code "38") (name "Net-(D2-PadC)") (class "Default")
      (node (ref "D2") (pin "C") (pinfunction "C_C") (pintype "passive"))
      (node (ref "R8") (pin "2") (pinfunction "2_2") (pintype "passive"))
    )
    (net (code "39") (name "Net-(D3-PadC)") (class "Default")
      (node (ref "D3") (pin "C") (pinfunction "C_C") (pintype "passive"))
      (node (ref "R10") (pin "2") (pinfunction "2_2") (pintype "passive"))
    )
    (net (code "40") (name "Net-(D4-PadC)") (class "Default")
      (node (ref "D4") (pin "C") (pinfunction "C_C") (pintype "passive"))
      (node (ref "R9") (pin "2") (pinfunction "2_2") (pintype "passive"))
    )
    (net (code "41") (name "Net-(D5-PadC)") (class "Default")
      (node (ref "D5") (pin "C") (pinfunction "C_C") (pintype "passive"))
      (node (ref "R11") (pin "2") (pinfunction "2_2") (pintype "passive"))
    )
    (net (code "42") (name "Net-(D6-PadC)") (class "Default")
      (node (ref "D6") (pin "C") (pinfunction "C_C") (pintype "passive"))
      (node (ref "R12") (pin "2") (pinfunction "2_2") (pintype "passive"))
    )
    (net (code "43") (name "Net-(D7-PadC)") (class "Default")
      (node (ref "D7") (pin "C") (pinfunction "C_C") (pintype "passive"))
      (node (ref "R13") (pin "2") (pinfunction "2_2") (pintype "passive"))
    )
    (net (code "44") (name "Net-(D8-PadC)") (class "Default")
      (node (ref "D8") (pin "C") (pinfunction "C_C") (pintype "passive"))
      (node (ref "R14") (pin "2") (pinfunction "2_2") (pintype "passive"))
    )
    (net (code "45") (name "Net-(D9-PadC)") (class "Default")
      (node (ref "D9") (pin "C") (pinfunction "C_C") (pintype "passive"))
      (node (ref "R15") (pin "2") (pinfunction "2_2") (pintype "passive"))
    )
    (net (code "46") (name "Net-(D10-PadC)") (class "Default")
      (node (ref "D10") (pin "C") (pinfunction "C_C") (pintype "passive"))
      (node (ref "R16") (pin "2") (pinfunction "2_2") (pintype "passive"))
    )
    (net (code "47") (name "Net-(D11-PadC)") (class "Default")
      (node (ref "D11") (pin "C") (pinfunction "C_C") (pintype "passive"))
      (node (ref "R17") (pin "2") (pinfunction "2_2") (pintype "passive"))
    )
    (net (code "48") (name "Net-(D12-PadC)") (class "Default")
      (node (ref "D12") (pin "C") (pinfunction "C_C") (pintype "passive"))
      (node (ref "R18") (pin "2") (pinfunction "2_2") (pintype "passive"))
    )
    (net (code "49") (name "Net-(D13-PadC)") (class "Default")
      (node (ref "D13") (pin "C") (pinfunction "C_C") (pintype "passive"))
      (node (ref "R19") (pin "2") (pinfunction "2_2") (pintype "passive"))
    )
    (net (code "50") (name "Net-(D14-PadC)") (class "Default")
      (node (ref "D14") (pin "C") (pinfunction "C_C") (pintype "passive"))
      (node (ref "R20") (pin "2") (pinfunction "2_2") (pintype "passive"))
    )
    (net (code "51") (name "Net-(D15-PadC)") (class "Default")
      (node (ref "D15") (pin "C") (pinfunction "C_C") (pintype "passive"))
      (node (ref "R21") (pin "2") (pinfunction "2_2") (pintype "passive"))
    )
    (net (code "52") (name "Net-(D16-PadC)") (class "Default")
      (node (ref "D16") (pin "C") (pinfunction "C_C") (pintype "passive"))
      (node (ref "R22") (pin "2") (pinfunction "2_2") (pintype "passive"))
    )
    (net (code "53") (name "Net-(D17-PadC)") (class "Default")
      (node (ref "D17") (pin "C") (pinfunction "C_C") (pintype "passive"))
      (node (ref "R23") (pin "2") (pinfunction "2_2") (pintype "passive"))
    )
    (net (code "54") (name "Net-(D18-PadC)") (class "Default")
      (node (ref "D18") (pin "C") (pinfunction "C_C") (pintype "passive"))
      (node (ref "R24") (pin "2") (pinfunction "2_2") (pintype "passive"))
    )
    (net (code "55") (name "Net-(D19-PadC)") (class "Default")
      (node (ref "D19") (pin "C") (pinfunction "C_C") (pintype "passive"))
      (node (ref "R25") (pin "2") (pinfunction "2_2") (pintype "passive"))
    )
    (net (code "56") (name "Net-(D20-PadC)") (class "Default")
      (node (ref "D20") (pin "C") (pinfunction "C_C") (pintype "passive"))
      (node (ref "R26") (pin "2") (pinfunction "2_2") (pintype "passive"))
    )
    (net (code "57") (name "Net-(D21-PadC)") (class "Default")
      (node (ref "D21") (pin "C") (pinfunction "C_C") (pintype "passive"))
      (node (ref "R30") (pin "2") (pinfunction "2_2") (pintype "passive"))
    )
    (net (code "58") (name "Net-(D22-PadC)") (class "Default")
      (node (ref "D22") (pin "C") (pinfunction "C_C") (pintype "passive"))
      (node (ref "R27") (pin "2") (pinfunction "2_2") (pintype "passive"))
    )
    (net (code "59") (name "Net-(D23-PadC)") (class "Default")
      (node (ref "D23") (pin "C") (pinfunction "C_C") (pintype "passive"))
      (node (ref "R28") (pin "2") (pinfunction "2_2") (pintype "passive"))
    )
    (net (code "60") (name "Net-(D24-PadC)") (class "Default")
      (node (ref "D24") (pin "C") (pinfunction "C_C") (pintype "passive"))
      (node (ref "R29") (pin "2") (pinfunction "2_2") (pintype "passive"))
    )
    (net (code "61") (name "Net-(D25-PadC)") (class "Default")
      (node (ref "D25") (pin "C") (pinfunction "C_C") (pintype "passive"))
      (node (ref "R31") (pin "2") (pinfunction "2_2") (pintype "passive"))
    )
    (net (code "62") (name "Net-(U14A-Q0)") (class "Default")
      (node (ref "D23") (pin "A") (pinfunction "A_A") (pintype "passive"))
      (node (ref "U14") (pin "3") (pinfunction "Q0_3") (pintype "tri_state"))
      (node (ref "U15") (pin "6") (pinfunction "A4_6") (pintype "bidirectional"))
    )
    (net (code "63") (name "Net-(U14A-Q1)") (class "Default")
      (node (ref "D24") (pin "A") (pinfunction "A_A") (pintype "passive"))
      (node (ref "U14") (pin "4") (pinfunction "Q1_4") (pintype "tri_state"))
      (node (ref "U15") (pin "7") (pinfunction "A5_7") (pintype "bidirectional"))
    )
    (net (code "64") (name "Net-(U14A-Q2)") (class "Default")
      (node (ref "D21") (pin "A") (pinfunction "A_A") (pintype "passive"))
      (node (ref "U14") (pin "5") (pinfunction "Q2_5") (pintype "tri_state"))
      (node (ref "U15") (pin "8") (pinfunction "A6_8") (pintype "bidirectional"))
    )
    (net (code "65") (name "Net-(U14A-Q3)") (class "Default")
      (node (ref "D25") (pin "A") (pinfunction "A_A") (pintype "passive"))
      (node (ref "U14") (pin "6") (pinfunction "Q3_6") (pintype "tri_state"))
      (node (ref "U15") (pin "9") (pinfunction "A7_9") (pintype "bidirectional"))
    )
    (net (code "66") (name "VCC") (class "Default")
      (node (ref "C10") (pin "2") (pinfunction "2_2") (pintype "passive"))
      (node (ref "C8") (pin "2") (pinfunction "2_2") (pintype "passive"))
      (node (ref "C9") (pin "2") (pinfunction "2_2") (pintype "passive"))
      (node (ref "U10") (pin "1") (pinfunction "A->B_1") (pintype "input"))
      (node (ref "U10") (pin "20") (pinfunction "VCC_20") (pintype "power_in"))
      (node (ref "U11") (pin "16") (pinfunction "VCC_16") (pintype "power_in"))
      (node (ref "U12") (pin "16") (pinfunction "VCC_16") (pintype "power_in"))
      (node (ref "U13") (pin "16") (pinfunction "VCC_16") (pintype "power_in"))
      (node (ref "U14") (pin "16") (pinfunction "VCC_16") (pintype "power_in"))
      (node (ref "U15") (pin "1") (pinfunction "A->B_1") (pintype "input"))
      (node (ref "U15") (pin "20") (pinfunction "VCC_20") (pintype "power_in"))
      (node (ref "U7") (pin "1") (pinfunction "A->B_1") (pintype "input"))
      (node (ref "U7") (pin "20") (pinfunction "VCC_20") (pintype "power_in"))
      (node (ref "U8") (pin "16") (pinfunction "VCC_16") (pintype "power_in"))
      (node (ref "U9") (pin "16") (pinfunction "VCC_16") (pintype "power_in"))
    )
  )
)
